# XMOS_chip.net
KiCad netlist of a schematic drawn in Altium Designer
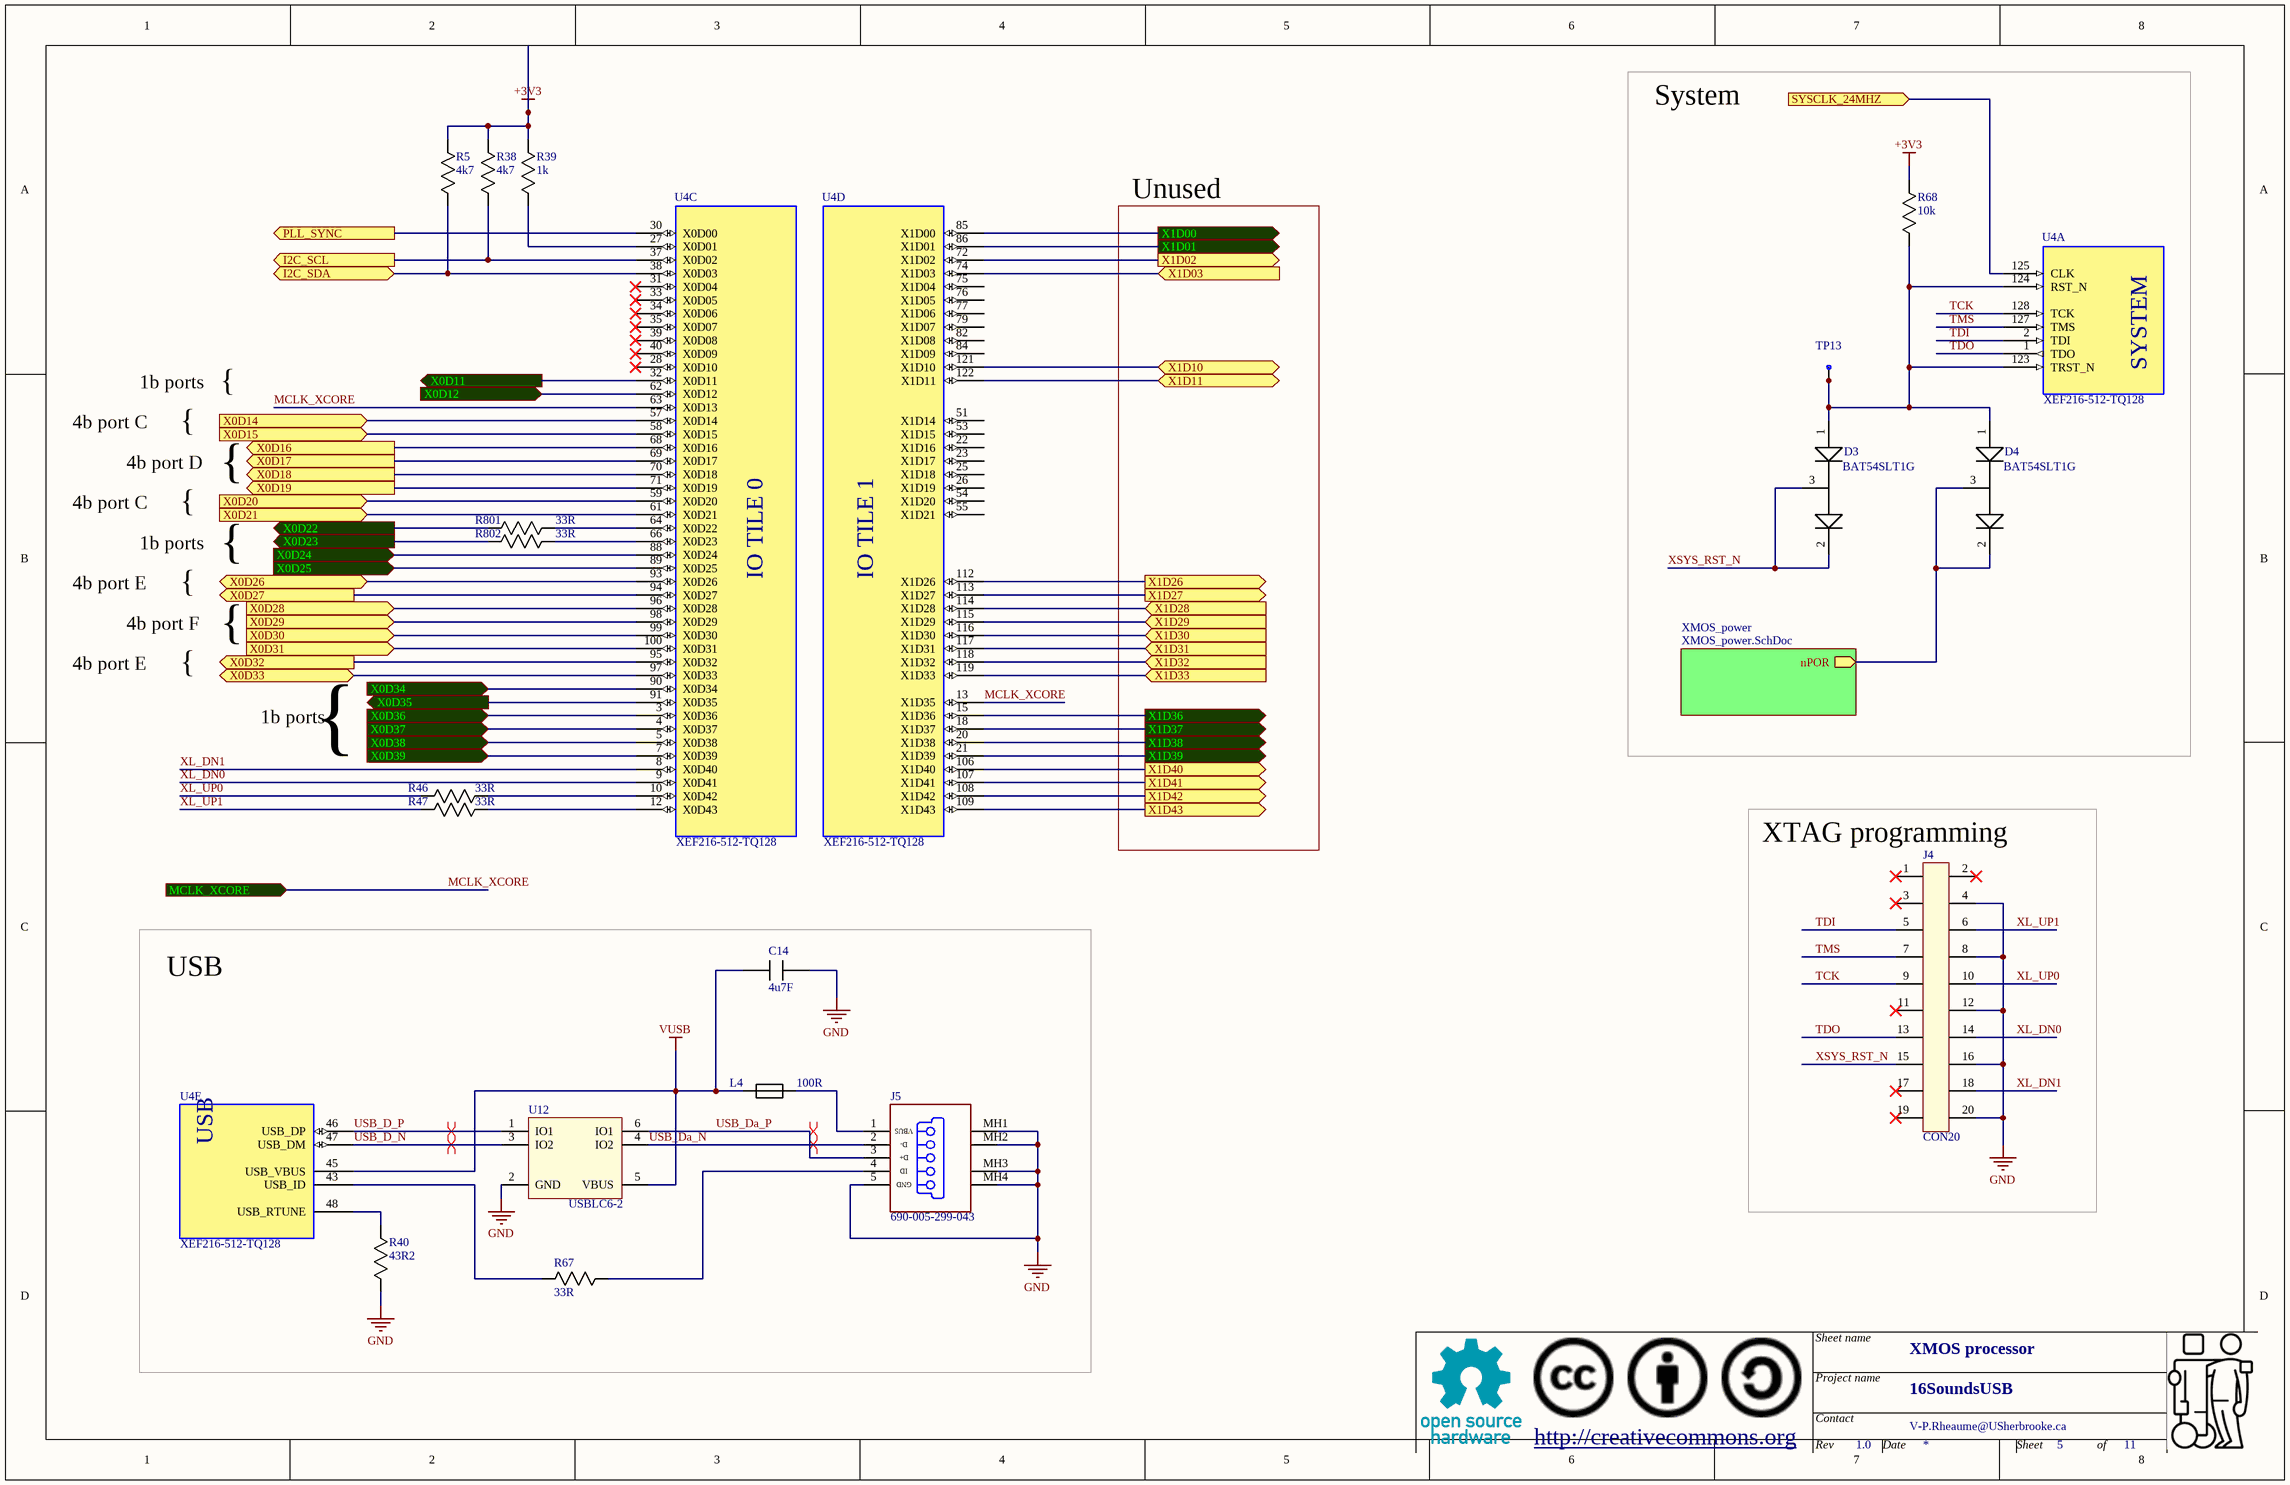
[diagram p0: XMOS_chip.SchDoc]

(export (version "E")
  (design (tool "Eeschema 10.0.6"))
  (components
    (comp (ref "C14")
      (value "4u7F")
      (footprint "0805")
      (description "Capacitor")
      (fields (field (name "MFG") "Samsung"))
      (libsource (lib "INTER_2014") (part "Capacitor"))
    )
    (comp (ref "D3")
      (value "Diode_dual")
      (footprint "SOT23_132")
      (description "Diode")
      (fields (field (name "MFG") "Onsemi") (field (name "MFG_PN") "BAT54SLT1G"))
      (libsource (lib "INTER_2014") (part "Diode_dual"))
    )
    (comp (ref "D4")
      (value "Diode_dual")
      (footprint "SOT23_132")
      (description "Diode")
      (fields (field (name "MFG") "Onsemi") (field (name "MFG_PN") "BAT54SLT1G"))
      (libsource (lib "INTER_2014") (part "Diode_dual"))
    )
    (comp (ref "J4")
      (value "CON20")
      (footprint "CONN20_100mils_pol_SMD")
      (description "20-pins")
      (fields (field (name "MFG") "CNC Tech"))
      (libsource (lib "INTER_2014") (part "CON20"))
    )
    (comp (ref "J5")
      (value "USB_MINIB_690-005-299-043")
      (footprint "CONN_USB_MINIB_690-005-299-043")
      (fields (field (name "MFG") "EDAC") (field (name "MFG_PN") "690-005-299-043"))
      (libsource (lib "INTER_2014") (part "USB_MINIB_690-005-299-043"))
    )
    (comp (ref "L4")
      (value "100R")
      (footprint "0805")
      (description "Ferrite")
      (fields (field (name "MFG") "Bourns"))
      (libsource (lib "INTER_2014") (part "Ferrite"))
    )
    (comp (ref "R5")
      (value "4k7")
      (footprint "0603")
      (description "Resistor")
      (fields (field (name "MFG") "Yageo"))
      (libsource (lib "INTER_2014") (part "Resistor"))
    )
    (comp (ref "R38")
      (value "4k7")
      (footprint "0603")
      (description "Resistor")
      (fields (field (name "MFG") "Yageo"))
      (libsource (lib "INTER_2014") (part "Resistor"))
    )
    (comp (ref "R39")
      (value "1k")
      (footprint "0603")
      (description "Resistor")
      (fields (field (name "MFG") "Yageo"))
      (libsource (lib "INTER_2014") (part "Resistor"))
    )
    (comp (ref "R40")
      (value "43R2")
      (footprint "0603")
      (description "Resistor")
      (fields (field (name "MFG") "Yageo"))
      (libsource (lib "INTER_2014") (part "Resistor"))
    )
    (comp (ref "R46")
      (value "33R")
      (footprint "0603")
      (description "Resistor")
      (fields (field (name "MFG") "Yageo"))
      (libsource (lib "INTER_2014") (part "Resistor"))
    )
    (comp (ref "R47")
      (value "33R")
      (footprint "0603")
      (description "Resistor")
      (fields (field (name "MFG") "Yageo"))
      (libsource (lib "INTER_2014") (part "Resistor"))
    )
    (comp (ref "R67")
      (value "33R")
      (footprint "0603")
      (description "Resistor")
      (fields (field (name "MFG") "Yageo"))
      (libsource (lib "INTER_2014") (part "Resistor"))
    )
    (comp (ref "R68")
      (value "10k")
      (footprint "0603")
      (description "Resistor")
      (fields (field (name "MFG") "Yageo"))
      (libsource (lib "INTER_2014") (part "Resistor"))
    )
    (comp (ref "R801")
      (value "33R")
      (footprint "0603")
      (description "Resistor")
      (fields (field (name "MFG") "Yageo"))
      (libsource (lib "INTER_2014") (part "Resistor"))
    )
    (comp (ref "R802")
      (value "33R")
      (footprint "0603")
      (description "Resistor")
      (fields (field (name "MFG") "Yageo"))
      (libsource (lib "INTER_2014") (part "Resistor"))
    )
    (comp (ref "TP13")
      (value "TESTPOINT")
      (footprint "0603")
      (description "Test point")
      (fields (field (name "MFG") "TE"))
      (libsource (lib "INTER_2014") (part "TESTPOINT"))
    )
    (comp (ref "U4")
      (value "~")
      (footprint "TQFP128_XMOS")
      (description "32-bit multicore microcontroller. 2 Tiles. 16 Logical Cores. 512KB SRAM. 1000MIPS. TQFP128.")
      (fields (field (name "MFG") "XMOS") (field (name "MFG_PN") "XEF216-512-TQ128"))
      (libsource (lib "INTER_2014") (part "XMOS_XEF216-512-TQ128"))
    )
    (comp (ref "U12")
      (value "USBLC6-2")
      (footprint "USBLC6-2")
      (description "USB overvoltage protection")
      (fields (field (name "MFG") "ST") (field (name "MFG_PN") "USBLC6-2"))
      (libsource (lib "INTER_2014") (part "USBLC6-2"))
    )
  )
  (nets
    (net (code "1") (name "+3V3") (class "Default")
      (node (ref "R38") (pin "1") (pintype "passive"))
      (node (ref "R39") (pin "1") (pintype "passive"))
      (node (ref "R5") (pin "1") (pintype "passive"))
      (node (ref "R68") (pin "1") (pintype "passive"))
    )
    (net (code "2") (name "/I2C_SCL") (class "Default")
      (node (ref "R38") (pin "2") (pintype "passive"))
      (node (ref "U4") (pin "37") (pinfunction "X0D02_37") (pintype "bidirectional"))
    )
    (net (code "3") (name "/I2C_SDA") (class "Default")
      (node (ref "R5") (pin "2") (pintype "passive"))
      (node (ref "U4") (pin "38") (pinfunction "X0D03_38") (pintype "bidirectional"))
    )
    (net (code "4") (name "/MCLK_XCORE") (class "Default")
      (node (ref "U4") (pin "13") (pinfunction "X1D35_13") (pintype "bidirectional"))
      (node (ref "U4") (pin "63") (pinfunction "X0D13_63") (pintype "bidirectional"))
    )
    (net (code "5") (name "/PLL_SYNC") (class "Default")
      (node (ref "U4") (pin "30") (pinfunction "X0D00_30") (pintype "bidirectional"))
    )
    (net (code "6") (name "/SYSCLK_24MHZ") (class "Default")
      (node (ref "U4") (pin "125") (pinfunction "CLK_125") (pintype "input"))
    )
    (net (code "7") (name "/TCK") (class "Default")
      (node (ref "J4") (pin "9") (pinfunction "9_9") (pintype "passive"))
      (node (ref "U4") (pin "128") (pinfunction "TCK_128") (pintype "input"))
    )
    (net (code "8") (name "/TDI") (class "Default")
      (node (ref "J4") (pin "5") (pinfunction "5_5") (pintype "passive"))
      (node (ref "U4") (pin "2") (pinfunction "TDI_2") (pintype "input"))
    )
    (net (code "9") (name "/TDO") (class "Default")
      (node (ref "J4") (pin "13") (pinfunction "13_13") (pintype "passive"))
      (node (ref "U4") (pin "1") (pinfunction "TDO_1") (pintype "output"))
    )
    (net (code "10") (name "/TMS") (class "Default")
      (node (ref "J4") (pin "7") (pinfunction "7_7") (pintype "passive"))
      (node (ref "U4") (pin "127") (pinfunction "TMS_127") (pintype "input"))
    )
    (net (code "11") (name "/USB_D_N") (class "Default")
      (node (ref "U12") (pin "3") (pinfunction "IO2_3") (pintype "passive"))
      (node (ref "U4") (pin "47") (pinfunction "USB_DM_47") (pintype "bidirectional"))
    )
    (net (code "12") (name "/USB_D_P") (class "Default")
      (node (ref "U12") (pin "1") (pinfunction "IO1_1") (pintype "passive"))
      (node (ref "U4") (pin "46") (pinfunction "USB_DP_46") (pintype "bidirectional"))
    )
    (net (code "13") (name "/USB_Da_N") (class "Default")
      (node (ref "J5") (pin "2") (pinfunction "D-_2") (pintype "passive"))
      (node (ref "U12") (pin "4") (pinfunction "IO2_4") (pintype "passive"))
    )
    (net (code "14") (name "/USB_Da_P") (class "Default")
      (node (ref "J5") (pin "3") (pinfunction "D+_3") (pintype "passive"))
      (node (ref "U12") (pin "6") (pinfunction "IO1_6") (pintype "passive"))
    )
    (net (code "15") (name "/X0D11") (class "Default")
      (node (ref "U4") (pin "32") (pinfunction "X0D11_32") (pintype "bidirectional"))
    )
    (net (code "16") (name "/X0D12") (class "Default")
      (node (ref "U4") (pin "62") (pinfunction "X0D12_62") (pintype "bidirectional"))
    )
    (net (code "17") (name "/X0D14") (class "Default")
      (node (ref "U4") (pin "57") (pinfunction "X0D14_57") (pintype "bidirectional"))
    )
    (net (code "18") (name "/X0D15") (class "Default")
      (node (ref "U4") (pin "58") (pinfunction "X0D15_58") (pintype "bidirectional"))
    )
    (net (code "19") (name "/X0D16") (class "Default")
      (node (ref "U4") (pin "68") (pinfunction "X0D16_68") (pintype "bidirectional"))
    )
    (net (code "20") (name "/X0D17") (class "Default")
      (node (ref "U4") (pin "69") (pinfunction "X0D17_69") (pintype "bidirectional"))
    )
    (net (code "21") (name "/X0D18") (class "Default")
      (node (ref "U4") (pin "70") (pinfunction "X0D18_70") (pintype "bidirectional"))
    )
    (net (code "22") (name "/X0D19") (class "Default")
      (node (ref "U4") (pin "71") (pinfunction "X0D19_71") (pintype "bidirectional"))
    )
    (net (code "23") (name "/X0D20") (class "Default")
      (node (ref "U4") (pin "59") (pinfunction "X0D20_59") (pintype "bidirectional"))
    )
    (net (code "24") (name "/X0D21") (class "Default")
      (node (ref "U4") (pin "61") (pinfunction "X0D21_61") (pintype "bidirectional"))
    )
    (net (code "25") (name "/X0D22") (class "Default") (node (ref "R801") (pin "1") (pintype "passive")))
    (net (code "26") (name "/X0D23") (class "Default") (node (ref "R802") (pin "1") (pintype "passive")))
    (net (code "27") (name "/X0D24") (class "Default")
      (node (ref "U4") (pin "88") (pinfunction "X0D24_88") (pintype "bidirectional"))
    )
    (net (code "28") (name "/X0D25") (class "Default")
      (node (ref "U4") (pin "89") (pinfunction "X0D25_89") (pintype "bidirectional"))
    )
    (net (code "29") (name "/X0D26") (class "Default")
      (node (ref "U4") (pin "93") (pinfunction "X0D26_93") (pintype "bidirectional"))
    )
    (net (code "30") (name "/X0D27") (class "Default")
      (node (ref "U4") (pin "94") (pinfunction "X0D27_94") (pintype "bidirectional"))
    )
    (net (code "31") (name "/X0D28") (class "Default")
      (node (ref "U4") (pin "96") (pinfunction "X0D28_96") (pintype "bidirectional"))
    )
    (net (code "32") (name "/X0D29") (class "Default")
      (node (ref "U4") (pin "98") (pinfunction "X0D29_98") (pintype "bidirectional"))
    )
    (net (code "33") (name "/X0D30") (class "Default")
      (node (ref "U4") (pin "99") (pinfunction "X0D30_99") (pintype "bidirectional"))
    )
    (net (code "34") (name "/X0D31") (class "Default")
      (node (ref "U4") (pin "100") (pinfunction "X0D31_100") (pintype "bidirectional"))
    )
    (net (code "35") (name "/X0D32") (class "Default")
      (node (ref "U4") (pin "95") (pinfunction "X0D32_95") (pintype "bidirectional"))
    )
    (net (code "36") (name "/X0D33") (class "Default")
      (node (ref "U4") (pin "97") (pinfunction "X0D33_97") (pintype "bidirectional"))
    )
    (net (code "37") (name "/X0D34") (class "Default")
      (node (ref "U4") (pin "90") (pinfunction "X0D34_90") (pintype "bidirectional"))
    )
    (net (code "38") (name "/X0D35") (class "Default")
      (node (ref "U4") (pin "91") (pinfunction "X0D35_91") (pintype "bidirectional"))
    )
    (net (code "39") (name "/X0D36") (class "Default")
      (node (ref "U4") (pin "3") (pinfunction "X0D36_3") (pintype "bidirectional"))
    )
    (net (code "40") (name "/X0D37") (class "Default")
      (node (ref "U4") (pin "4") (pinfunction "X0D37_4") (pintype "bidirectional"))
    )
    (net (code "41") (name "/X0D38") (class "Default")
      (node (ref "U4") (pin "5") (pinfunction "X0D38_5") (pintype "bidirectional"))
    )
    (net (code "42") (name "/X0D39") (class "Default")
      (node (ref "U4") (pin "7") (pinfunction "X0D39_7") (pintype "bidirectional"))
    )
    (net (code "43") (name "/X1D00") (class "Default")
      (node (ref "U4") (pin "85") (pinfunction "X1D00_85") (pintype "bidirectional"))
    )
    (net (code "44") (name "/X1D01") (class "Default")
      (node (ref "U4") (pin "86") (pinfunction "X1D01_86") (pintype "bidirectional"))
    )
    (net (code "45") (name "/X1D02") (class "Default")
      (node (ref "U4") (pin "72") (pinfunction "X1D02_72") (pintype "bidirectional"))
    )
    (net (code "46") (name "/X1D03") (class "Default")
      (node (ref "U4") (pin "74") (pinfunction "X1D03_74") (pintype "bidirectional"))
    )
    (net (code "47") (name "/X1D10") (class "Default")
      (node (ref "U4") (pin "121") (pinfunction "X1D10_121") (pintype "bidirectional"))
    )
    (net (code "48") (name "/X1D11") (class "Default")
      (node (ref "U4") (pin "122") (pinfunction "X1D11_122") (pintype "bidirectional"))
    )
    (net (code "49") (name "/X1D26") (class "Default")
      (node (ref "U4") (pin "112") (pinfunction "X1D26_112") (pintype "bidirectional"))
    )
    (net (code "50") (name "/X1D27") (class "Default")
      (node (ref "U4") (pin "113") (pinfunction "X1D27_113") (pintype "bidirectional"))
    )
    (net (code "51") (name "/X1D28") (class "Default")
      (node (ref "U4") (pin "114") (pinfunction "X1D28_114") (pintype "bidirectional"))
    )
    (net (code "52") (name "/X1D29") (class "Default")
      (node (ref "U4") (pin "115") (pinfunction "X1D29_115") (pintype "bidirectional"))
    )
    (net (code "53") (name "/X1D30") (class "Default")
      (node (ref "U4") (pin "116") (pinfunction "X1D30_116") (pintype "bidirectional"))
    )
    (net (code "54") (name "/X1D31") (class "Default")
      (node (ref "U4") (pin "117") (pinfunction "X1D31_117") (pintype "bidirectional"))
    )
    (net (code "55") (name "/X1D32") (class "Default")
      (node (ref "U4") (pin "118") (pinfunction "X1D32_118") (pintype "bidirectional"))
    )
    (net (code "56") (name "/X1D33") (class "Default")
      (node (ref "U4") (pin "119") (pinfunction "X1D33_119") (pintype "bidirectional"))
    )
    (net (code "57") (name "/X1D36") (class "Default")
      (node (ref "U4") (pin "15") (pinfunction "X1D36_15") (pintype "bidirectional"))
    )
    (net (code "58") (name "/X1D37") (class "Default")
      (node (ref "U4") (pin "18") (pinfunction "X1D37_18") (pintype "bidirectional"))
    )
    (net (code "59") (name "/X1D38") (class "Default")
      (node (ref "U4") (pin "20") (pinfunction "X1D38_20") (pintype "bidirectional"))
    )
    (net (code "60") (name "/X1D39") (class "Default")
      (node (ref "U4") (pin "21") (pinfunction "X1D39_21") (pintype "bidirectional"))
    )
    (net (code "61") (name "/X1D40") (class "Default")
      (node (ref "U4") (pin "106") (pinfunction "X1D40_106") (pintype "bidirectional"))
    )
    (net (code "62") (name "/X1D41") (class "Default")
      (node (ref "U4") (pin "107") (pinfunction "X1D41_107") (pintype "bidirectional"))
    )
    (net (code "63") (name "/X1D42") (class "Default")
      (node (ref "U4") (pin "108") (pinfunction "X1D42_108") (pintype "bidirectional"))
    )
    (net (code "64") (name "/X1D43") (class "Default")
      (node (ref "U4") (pin "109") (pinfunction "X1D43_109") (pintype "bidirectional"))
    )
    (net (code "65") (name "/XL_DN0") (class "Default")
      (node (ref "J4") (pin "14") (pinfunction "14_14") (pintype "passive"))
      (node (ref "U4") (pin "9") (pinfunction "X0D41_9") (pintype "bidirectional"))
    )
    (net (code "66") (name "/XL_DN1") (class "Default")
      (node (ref "J4") (pin "18") (pinfunction "18_18") (pintype "passive"))
      (node (ref "U4") (pin "8") (pinfunction "X0D40_8") (pintype "bidirectional"))
    )
    (net (code "67") (name "/XL_UP0") (class "Default")
      (node (ref "J4") (pin "10") (pinfunction "10_10") (pintype "passive"))
      (node (ref "R46") (pin "1") (pintype "passive"))
    )
    (net (code "68") (name "/XL_UP1") (class "Default")
      (node (ref "J4") (pin "6") (pinfunction "6_6") (pintype "passive"))
      (node (ref "R47") (pin "1") (pintype "passive"))
    )
    (net (code "69") (name "/XSYS_RST_N") (class "Default")
      (node (ref "D3") (pin "2") (pinfunction "K_2") (pintype "passive"))
      (node (ref "D3") (pin "3") (pinfunction "AK_3") (pintype "passive"))
      (node (ref "J4") (pin "15") (pinfunction "15_15") (pintype "passive"))
    )
    (net (code "70") (name "/nPOR") (class "Default")
      (node (ref "D4") (pin "2") (pinfunction "K_2") (pintype "passive"))
      (node (ref "D4") (pin "3") (pinfunction "AK_3") (pintype "passive"))
    )
    (net (code "71") (name "GND") (class "Default")
      (node (ref "C14") (pin "2") (pintype "passive"))
      (node (ref "J4") (pin "12") (pinfunction "12_12") (pintype "passive"))
      (node (ref "J4") (pin "16") (pinfunction "16_16") (pintype "passive"))
      (node (ref "J4") (pin "20") (pinfunction "20_20") (pintype "passive"))
      (node (ref "J4") (pin "4") (pintype "passive"))
      (node (ref "J4") (pin "8") (pinfunction "8_8") (pintype "passive"))
      (node (ref "J5") (pin "5") (pinfunction "GND_5") (pintype "passive"))
      (node (ref "J5") (pin "MH1") (pinfunction "Tab_MH1") (pintype "passive"))
      (node (ref "J5") (pin "MH2") (pinfunction "Tab_MH2") (pintype "passive"))
      (node (ref "J5") (pin "MH3") (pinfunction "Tab_MH3") (pintype "passive"))
      (node (ref "J5") (pin "MH4") (pinfunction "Tab_MH4") (pintype "passive"))
      (node (ref "R40") (pin "1") (pintype "passive"))
      (node (ref "U12") (pin "2") (pinfunction "GND_2") (pintype "passive"))
    )
    (net (code "72") (name "Net-(J5-NC)") (class "Default")
      (node (ref "J5") (pin "4") (pinfunction "NC_4") (pintype "passive"))
      (node (ref "R67") (pin "1") (pintype "passive"))
    )
    (net (code "73") (name "Net-(J5-V_BUS_(5V))") (class "Default")
      (node (ref "J5") (pin "1") (pinfunction "V_BUS_(5V)_1") (pintype "passive"))
      (node (ref "L4") (pin "2") (pintype "passive"))
    )
    (net (code "74") (name "Net-(U4A-RST_N)") (class "Default")
      (node (ref "D3") (pin "1") (pinfunction "K_1") (pintype "passive"))
      (node (ref "D4") (pin "1") (pinfunction "K_1") (pintype "passive"))
      (node (ref "R68") (pin "2") (pintype "passive"))
      (node (ref "TP13") (pin "1") (pintype "passive"))
      (node (ref "TP13") (pin "2") (pintype "passive"))
      (node (ref "U4") (pin "123") (pinfunction "TRST_N_123") (pintype "input"))
      (node (ref "U4") (pin "124") (pinfunction "RST_N_124") (pintype "input"))
    )
    (net (code "75") (name "Net-(U4C-X0D01)") (class "Default")
      (node (ref "R39") (pin "2") (pintype "passive"))
      (node (ref "U4") (pin "27") (pinfunction "X0D01_27") (pintype "bidirectional"))
    )
    (net (code "76") (name "Net-(U4C-X0D22)") (class "Default")
      (node (ref "R801") (pin "2") (pintype "passive"))
      (node (ref "U4") (pin "64") (pinfunction "X0D22_64") (pintype "bidirectional"))
    )
    (net (code "77") (name "Net-(U4C-X0D23)") (class "Default")
      (node (ref "R802") (pin "2") (pintype "passive"))
      (node (ref "U4") (pin "66") (pinfunction "X0D23_66") (pintype "bidirectional"))
    )
    (net (code "78") (name "Net-(U4C-X0D42)") (class "Default")
      (node (ref "R46") (pin "2") (pintype "passive"))
      (node (ref "U4") (pin "10") (pinfunction "X0D42_10") (pintype "bidirectional"))
    )
    (net (code "79") (name "Net-(U4C-X0D43)") (class "Default")
      (node (ref "R47") (pin "2") (pintype "passive"))
      (node (ref "U4") (pin "12") (pinfunction "X0D43_12") (pintype "bidirectional"))
    )
    (net (code "80") (name "Net-(U4E-USB_ID)") (class "Default")
      (node (ref "R67") (pin "2") (pintype "passive"))
      (node (ref "U4") (pin "43") (pinfunction "USB_ID_43") (pintype "passive"))
    )
    (net (code "81") (name "Net-(U4E-USB_RTUNE)") (class "Default")
      (node (ref "R40") (pin "2") (pintype "passive"))
      (node (ref "U4") (pin "48") (pinfunction "USB_RTUNE_48") (pintype "passive"))
    )
    (net (code "82") (name "VUSB") (class "Default")
      (node (ref "C14") (pin "1") (pintype "passive"))
      (node (ref "L4") (pin "1") (pintype "passive"))
      (node (ref "U12") (pin "5") (pinfunction "VBUS_5") (pintype "passive"))
      (node (ref "U4") (pin "45") (pinfunction "USB_VBUS_45") (pintype "passive"))
    )
    (net (code "83") (name "unconnected-(J4-Pad1)") (class "Default")
      (node (ref "J4") (pin "1") (pintype "passive+no_connect"))
    )
    (net (code "84") (name "unconnected-(J4-Pad2)") (class "Default")
      (node (ref "J4") (pin "2") (pintype "passive+no_connect"))
    )
    (net (code "85") (name "unconnected-(J4-Pad3)") (class "Default")
      (node (ref "J4") (pin "3") (pintype "passive+no_connect"))
    )
    (net (code "86") (name "unconnected-(J4-Pad11)") (class "Default")
      (node (ref "J4") (pin "11") (pinfunction "11_11") (pintype "passive+no_connect"))
    )
    (net (code "87") (name "unconnected-(J4-Pad17)") (class "Default")
      (node (ref "J4") (pin "17") (pinfunction "17_17") (pintype "passive+no_connect"))
    )
    (net (code "88") (name "unconnected-(J4-Pad19)") (class "Default")
      (node (ref "J4") (pin "19") (pinfunction "19_19") (pintype "passive+no_connect"))
    )
    (net (code "89") (name "unconnected-(U4C-X0D04-Pad31)") (class "Default")
      (node (ref "U4") (pin "31") (pinfunction "X0D04_31") (pintype "bidirectional+no_connect"))
    )
    (net (code "90") (name "unconnected-(U4C-X0D05-Pad33)") (class "Default")
      (node (ref "U4") (pin "33") (pinfunction "X0D05_33") (pintype "bidirectional+no_connect"))
    )
    (net (code "91") (name "unconnected-(U4C-X0D06-Pad34)") (class "Default")
      (node (ref "U4") (pin "34") (pinfunction "X0D06_34") (pintype "bidirectional+no_connect"))
    )
    (net (code "92") (name "unconnected-(U4C-X0D07-Pad35)") (class "Default")
      (node (ref "U4") (pin "35") (pinfunction "X0D07_35") (pintype "bidirectional+no_connect"))
    )
    (net (code "93") (name "unconnected-(U4C-X0D08-Pad39)") (class "Default")
      (node (ref "U4") (pin "39") (pinfunction "X0D08_39") (pintype "bidirectional+no_connect"))
    )
    (net (code "94") (name "unconnected-(U4C-X0D09-Pad40)") (class "Default")
      (node (ref "U4") (pin "40") (pinfunction "X0D09_40") (pintype "bidirectional+no_connect"))
    )
    (net (code "95") (name "unconnected-(U4C-X0D10-Pad28)") (class "Default")
      (node (ref "U4") (pin "28") (pinfunction "X0D10_28") (pintype "bidirectional+no_connect"))
    )
    (net (code "96") (name "unconnected-(U4D-X1D04-Pad75)") (class "Default")
      (node (ref "U4") (pin "75") (pinfunction "X1D04_75") (pintype "bidirectional"))
    )
    (net (code "97") (name "unconnected-(U4D-X1D05-Pad76)") (class "Default")
      (node (ref "U4") (pin "76") (pinfunction "X1D05_76") (pintype "bidirectional"))
    )
    (net (code "98") (name "unconnected-(U4D-X1D06-Pad77)") (class "Default")
      (node (ref "U4") (pin "77") (pinfunction "X1D06_77") (pintype "bidirectional"))
    )
    (net (code "99") (name "unconnected-(U4D-X1D07-Pad79)") (class "Default")
      (node (ref "U4") (pin "79") (pinfunction "X1D07_79") (pintype "bidirectional"))
    )
    (net (code "100") (name "unconnected-(U4D-X1D08-Pad82)") (class "Default")
      (node (ref "U4") (pin "82") (pinfunction "X1D08_82") (pintype "bidirectional"))
    )
    (net (code "101") (name "unconnected-(U4D-X1D09-Pad84)") (class "Default")
      (node (ref "U4") (pin "84") (pinfunction "X1D09_84") (pintype "bidirectional"))
    )
    (net (code "102") (name "unconnected-(U4D-X1D14-Pad51)") (class "Default")
      (node (ref "U4") (pin "51") (pinfunction "X1D14_51") (pintype "bidirectional"))
    )
    (net (code "103") (name "unconnected-(U4D-X1D15-Pad53)") (class "Default")
      (node (ref "U4") (pin "53") (pinfunction "X1D15_53") (pintype "bidirectional"))
    )
    (net (code "104") (name "unconnected-(U4D-X1D16-Pad22)") (class "Default")
      (node (ref "U4") (pin "22") (pinfunction "X1D16_22") (pintype "bidirectional"))
    )
    (net (code "105") (name "unconnected-(U4D-X1D17-Pad23)") (class "Default")
      (node (ref "U4") (pin "23") (pinfunction "X1D17_23") (pintype "bidirectional"))
    )
    (net (code "106") (name "unconnected-(U4D-X1D18-Pad25)") (class "Default")
      (node (ref "U4") (pin "25") (pinfunction "X1D18_25") (pintype "bidirectional"))
    )
    (net (code "107") (name "unconnected-(U4D-X1D19-Pad26)") (class "Default")
      (node (ref "U4") (pin "26") (pinfunction "X1D19_26") (pintype "bidirectional"))
    )
    (net (code "108") (name "unconnected-(U4D-X1D20-Pad54)") (class "Default")
      (node (ref "U4") (pin "54") (pinfunction "X1D20_54") (pintype "bidirectional"))
    )
    (net (code "109") (name "unconnected-(U4D-X1D21-Pad55)") (class "Default")
      (node (ref "U4") (pin "55") (pinfunction "X1D21_55") (pintype "bidirectional"))
    )
  )
)
